# EthernetPlug.net
KiCad netlist of a schematic drawn in EAGLE
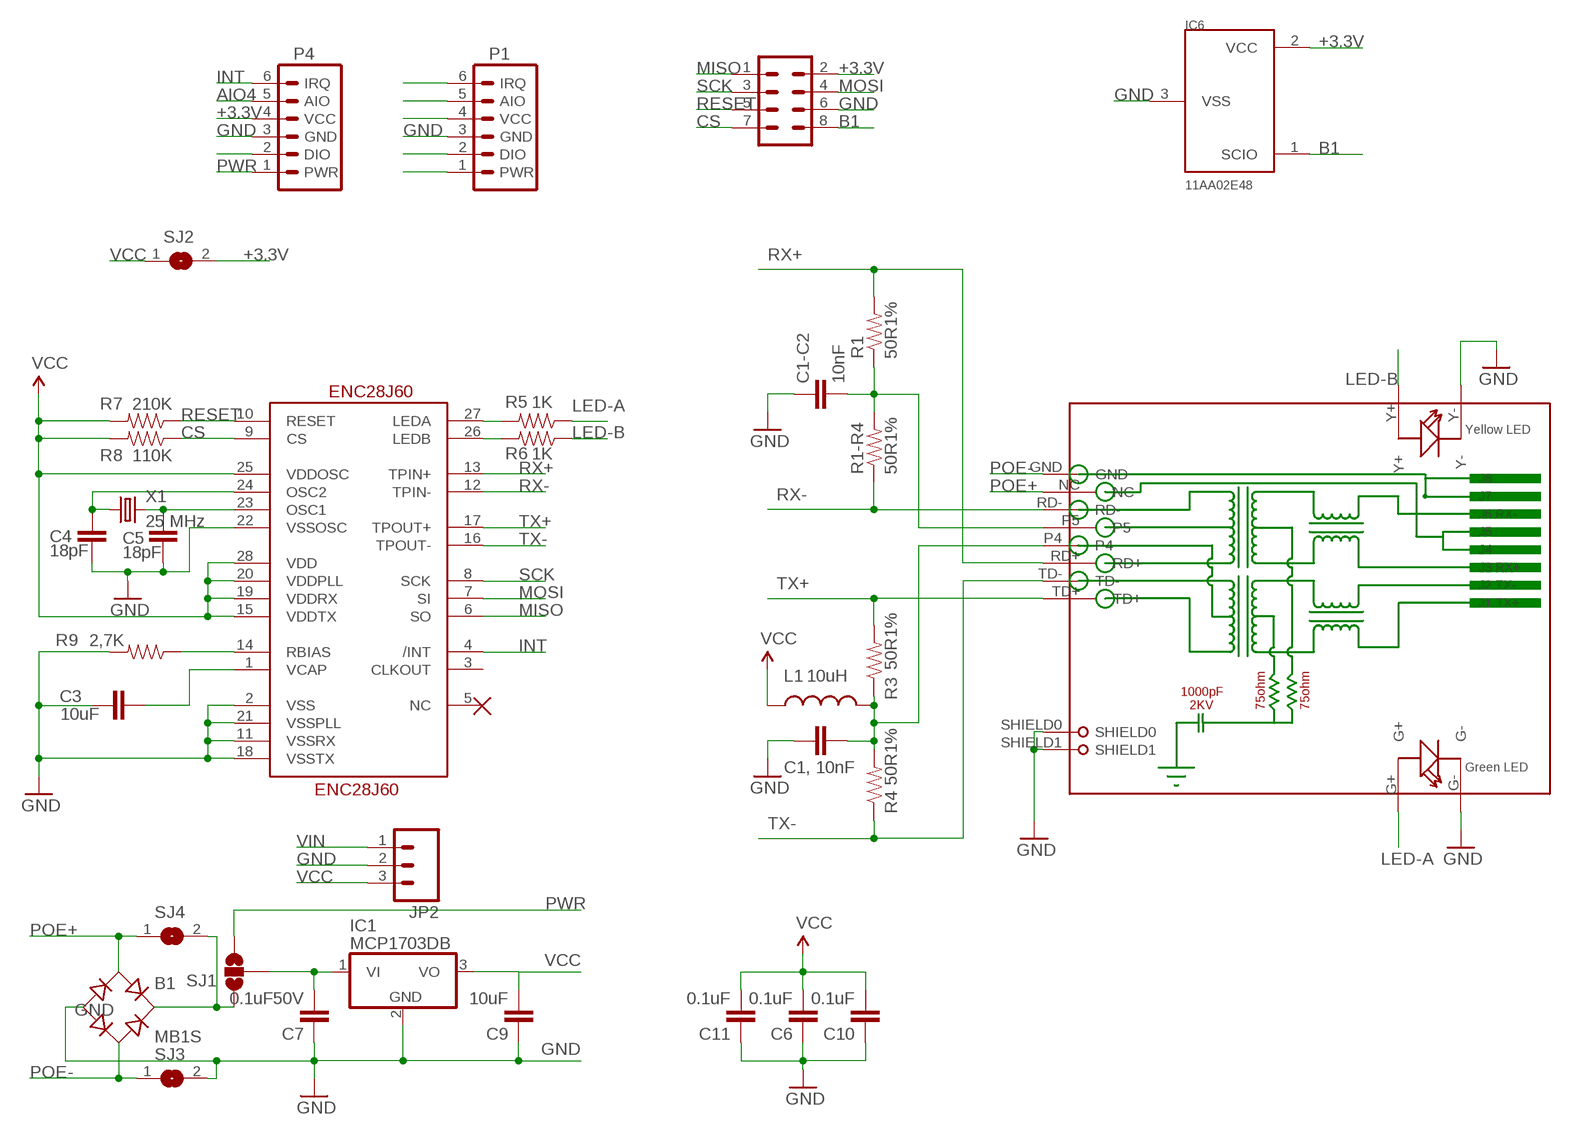
[diagram p0: schematic, sheet 1]

(export (version "E")
  (design (tool "Eeschema 10.0.6"))
  (components
    (comp (ref "B1")
      (value "MB1S")
      (footprint "eagle-import:SOIC-4")
      (libsource (lib "eagle-import") (part "MBS1"))
    )
    (comp (ref "C1,")
      (value "10nF")
      (footprint "eagle-import:0603-CAP")
      (libsource (lib "eagle-import") (part "CAP0603-CAP"))
    )
    (comp (ref "C1-C2")
      (value "10nF")
      (footprint "eagle-import:0603-CAP")
      (libsource (lib "eagle-import") (part "CAP0603-CAP"))
    )
    (comp (ref "C3")
      (value "10uF")
      (footprint "eagle-import:0603-CAP")
      (libsource (lib "eagle-import") (part "CAP0603-CAP"))
    )
    (comp (ref "C4")
      (value "18pF")
      (footprint "eagle-import:0603-CAP")
      (libsource (lib "eagle-import") (part "CAP0603-CAP"))
    )
    (comp (ref "C5")
      (value "18pF")
      (footprint "eagle-import:0603-CAP")
      (libsource (lib "eagle-import") (part "CAP0603-CAP"))
    )
    (comp (ref "C6")
      (value "0.1uF")
      (footprint "eagle-import:0603-CAP")
      (libsource (lib "eagle-import") (part "CAP0603-CAP"))
    )
    (comp (ref "C7")
      (value "0.1uF50V")
      (footprint "eagle-import:0603-CAP")
      (libsource (lib "eagle-import") (part "CAP0603-CAP"))
    )
    (comp (ref "C9")
      (value "10uF")
      (footprint "eagle-import:0603-CAP")
      (libsource (lib "eagle-import") (part "CAP0603-CAP"))
    )
    (comp (ref "C10")
      (value "0.1uF")
      (footprint "eagle-import:0603-CAP")
      (libsource (lib "eagle-import") (part "CAP0603-CAP"))
    )
    (comp (ref "C11")
      (value "0.1uF")
      (footprint "eagle-import:0603-CAP")
      (libsource (lib "eagle-import") (part "CAP0603-CAP"))
    )
    (comp (ref "ENC28J60")
      (value "ENC28J60")
      (footprint "eagle-import:SSOP28DB")
      (libsource (lib "eagle-import") (part "ENC28J60"))
    )
    (comp (ref "IC1")
      (value "MCP1703DB")
      (footprint "eagle-import:SOT223")
      (libsource (lib "eagle-import") (part "MCP1703DB"))
    )
    (comp (ref "IC6")
      (value "11AA02E48")
      (footprint "eagle-import:SOT23")
      (libsource (lib "eagle-import") (part "11AA02E48"))
    )
    (comp (ref "ISP")
      (value "MA04-2")
      (footprint "eagle-import:MA04-2")
      (libsource (lib "eagle-import") (part "MA04-2"))
    )
    (comp (ref "JP2")
      (value "M03PTH")
      (footprint "eagle-import:1X03")
      (libsource (lib "eagle-import") (part "M03PTH"))
    )
    (comp (ref "L1")
      (value "10uH")
      (footprint "eagle-import:0603")
      (libsource (lib "eagle-import") (part "INDUCTOR0603"))
    )
    (comp (ref "P1")
      (value "JEEPORT-FEMALE")
      (footprint "eagle-import:1X06_FEMALE_LOCK.010")
      (libsource (lib "eagle-import") (part "JEEPORT-FEMALE"))
    )
    (comp (ref "P4")
      (value "JEEPORT-FEMALE")
      (footprint "eagle-import:1X06_FEMALE_LOCK.010")
      (libsource (lib "eagle-import") (part "JEEPORT-FEMALE"))
    )
    (comp (ref "R1")
      (value "50R1%")
      (footprint "eagle-import:0603-RES")
      (libsource (lib "eagle-import") (part "RESISTOR0603-RES"))
    )
    (comp (ref "R1-R4")
      (value "50R1%")
      (footprint "eagle-import:0603-RES")
      (libsource (lib "eagle-import") (part "RESISTOR0603-RES"))
    )
    (comp (ref "R3")
      (value "50R1%")
      (footprint "eagle-import:0603-RES")
      (libsource (lib "eagle-import") (part "RESISTOR0603-RES"))
    )
    (comp (ref "R4")
      (value "50R1%")
      (footprint "eagle-import:0603-RES")
      (libsource (lib "eagle-import") (part "RESISTOR0603-RES"))
    )
    (comp (ref "R5")
      (value "1K")
      (footprint "eagle-import:0603-RES")
      (libsource (lib "eagle-import") (part "RESISTOR0603-RES"))
    )
    (comp (ref "R6")
      (value "1K")
      (footprint "eagle-import:0603-RES")
      (libsource (lib "eagle-import") (part "RESISTOR0603-RES"))
    )
    (comp (ref "R7")
      (value "210K")
      (footprint "eagle-import:0603-RES")
      (libsource (lib "eagle-import") (part "RESISTOR0603-RES"))
    )
    (comp (ref "R8")
      (value "110K")
      (footprint "eagle-import:0603-RES")
      (libsource (lib "eagle-import") (part "RESISTOR0603-RES"))
    )
    (comp (ref "R9")
      (value "2,7K")
      (footprint "eagle-import:0603-RES")
      (libsource (lib "eagle-import") (part "RESISTOR0603-RES"))
    )
    (comp (ref "RJ1")
      (value "HLJ-6115ANL")
      (footprint "eagle-import:HR911105A")
      (libsource (lib "eagle-import") (part "HLJ-6115ANL"))
    )
    (comp (ref "SJ1")
      (value "SOLDERJUMPER_2WAYT")
      (footprint "eagle-import:SJ_2")
      (libsource (lib "eagle-import") (part "SOLDERJUMPER_2WAYT"))
    )
    (comp (ref "SJ2") (value "SJ") (footprint "eagle-import:SJ") (libsource (lib "eagle-import") (part "SJ")))
    (comp (ref "SJ3") (value "SJ") (footprint "eagle-import:SJ") (libsource (lib "eagle-import") (part "SJ")))
    (comp (ref "SJ4") (value "SJ") (footprint "eagle-import:SJ") (libsource (lib "eagle-import") (part "SJ")))
    (comp (ref "X1")
      (value "25 MHz")
      (footprint "eagle-import:CRYSTAL-SMD-3.2X2.5")
      (libsource (lib "eagle-import") (part "CRYSTAL3.2X2.5"))
    )
  )
  (nets
    (net (code "1") (name "/+3.3V") (class "Default")
      (node (ref "IC6") (pin "2") (pinfunction "VCC_2") (pintype "bidirectional"))
      (node (ref "ISP") (pin "2") (pinfunction "2_2") (pintype "passive"))
      (node (ref "P4") (pin "4") (pinfunction "VCC_4") (pintype "power_in"))
      (node (ref "SJ2") (pin "2") (pinfunction "2_2") (pintype "passive"))
    )
    (net (code "2") (name "/AIO4") (class "Default")
      (node (ref "P4") (pin "5") (pinfunction "AIO_5") (pintype "bidirectional"))
    )
    (net (code "3") (name "/B1") (class "Default")
      (node (ref "IC6") (pin "1") (pinfunction "SCIO_1") (pintype "bidirectional"))
      (node (ref "ISP") (pin "8") (pinfunction "8_8") (pintype "passive"))
    )
    (net (code "4") (name "/CS") (class "Default")
      (node (ref "ENC28J60") (pin "9") (pinfunction "CS_9") (pintype "bidirectional"))
      (node (ref "ISP") (pin "7") (pinfunction "7_7") (pintype "passive"))
      (node (ref "R8") (pin "1") (pinfunction "1_1") (pintype "passive"))
    )
    (net (code "5") (name "/INT") (class "Default")
      (node (ref "ENC28J60") (pin "4") (pinfunction "/INT_4") (pintype "bidirectional"))
      (node (ref "P4") (pin "6") (pinfunction "IRQ_6") (pintype "bidirectional"))
    )
    (net (code "6") (name "/LED-A") (class "Default")
      (node (ref "R5") (pin "1") (pinfunction "1_1") (pintype "passive"))
      (node (ref "RJ1") (pin "G+") (pinfunction "G+_G+") (pintype "bidirectional"))
    )
    (net (code "7") (name "/LED-B") (class "Default")
      (node (ref "R6") (pin "1") (pinfunction "1_1") (pintype "passive"))
      (node (ref "RJ1") (pin "Y+") (pinfunction "Y+_Y+") (pintype "bidirectional"))
    )
    (net (code "8") (name "/MISO") (class "Default")
      (node (ref "ENC28J60") (pin "6") (pinfunction "SO_6") (pintype "bidirectional"))
      (node (ref "ISP") (pin "1") (pinfunction "1_1") (pintype "passive"))
    )
    (net (code "9") (name "/MOSI") (class "Default")
      (node (ref "ENC28J60") (pin "7") (pinfunction "SI_7") (pintype "bidirectional"))
      (node (ref "ISP") (pin "4") (pinfunction "4_4") (pintype "passive"))
    )
    (net (code "10") (name "/POE+") (class "Default")
      (node (ref "B1") (pin "~1") (pinfunction "AC1_~1") (pintype "passive"))
      (node (ref "RJ1") (pin "NC") (pinfunction "NC_NC") (pintype "bidirectional"))
      (node (ref "SJ4") (pin "1") (pinfunction "1_1") (pintype "passive"))
    )
    (net (code "11") (name "/POE-") (class "Default")
      (node (ref "B1") (pin "~2") (pinfunction "AC2_~2") (pintype "passive"))
      (node (ref "RJ1") (pin "GND") (pinfunction "GND_GND") (pintype "bidirectional"))
      (node (ref "SJ3") (pin "1") (pinfunction "1_1") (pintype "passive"))
    )
    (net (code "12") (name "/PWR") (class "Default")
      (node (ref "P4") (pin "1") (pinfunction "PWR_1") (pintype "power_in"))
      (node (ref "SJ1") (pin "3") (pinfunction "3_3") (pintype "passive"))
    )
    (net (code "13") (name "/RESET") (class "Default")
      (node (ref "ENC28J60") (pin "10") (pinfunction "RESET_10") (pintype "bidirectional"))
      (node (ref "ISP") (pin "5") (pinfunction "5_5") (pintype "passive"))
      (node (ref "R7") (pin "1") (pinfunction "1_1") (pintype "passive"))
    )
    (net (code "14") (name "/RX+") (class "Default")
      (node (ref "ENC28J60") (pin "13") (pinfunction "TPIN+_13") (pintype "bidirectional"))
      (node (ref "R1") (pin "2") (pinfunction "2_2") (pintype "passive"))
      (node (ref "RJ1") (pin "RD+") (pinfunction "RD+_RD+") (pintype "bidirectional"))
    )
    (net (code "15") (name "/RX-") (class "Default")
      (node (ref "ENC28J60") (pin "12") (pinfunction "TPIN-_12") (pintype "bidirectional"))
      (node (ref "R1-R4") (pin "1") (pinfunction "1_1") (pintype "passive"))
      (node (ref "RJ1") (pin "RD-") (pinfunction "RD-_RD-") (pintype "bidirectional"))
    )
    (net (code "16") (name "/SCK") (class "Default")
      (node (ref "ENC28J60") (pin "8") (pinfunction "SCK_8") (pintype "bidirectional"))
      (node (ref "ISP") (pin "3") (pinfunction "3_3") (pintype "passive"))
    )
    (net (code "17") (name "/TX+") (class "Default")
      (node (ref "ENC28J60") (pin "17") (pinfunction "TPOUT+_17") (pintype "bidirectional"))
      (node (ref "R3") (pin "2") (pinfunction "2_2") (pintype "passive"))
      (node (ref "RJ1") (pin "TD+") (pinfunction "TD+_TD+") (pintype "bidirectional"))
    )
    (net (code "18") (name "/TX-") (class "Default")
      (node (ref "ENC28J60") (pin "16") (pinfunction "TPOUT-_16") (pintype "bidirectional"))
      (node (ref "R4") (pin "1") (pinfunction "1_1") (pintype "passive"))
      (node (ref "RJ1") (pin "TD-") (pinfunction "TD-_TD-") (pintype "bidirectional"))
    )
    (net (code "19") (name "/VIN") (class "Default")
      (node (ref "C7") (pin "2") (pinfunction "2_2") (pintype "passive"))
      (node (ref "IC1") (pin "1") (pinfunction "VI_1") (pintype "input"))
      (node (ref "JP2") (pin "1") (pinfunction "1_1") (pintype "passive"))
      (node (ref "SJ1") (pin "2") (pinfunction "2_2") (pintype "passive"))
    )
    (net (code "20") (name "GND") (class "Default")
      (node (ref "B1") (pin "-") (pinfunction "-_-") (pintype "passive"))
      (node (ref "C1,") (pin "1") (pinfunction "1_1") (pintype "passive"))
      (node (ref "C1-C2") (pin "1") (pinfunction "1_1") (pintype "passive"))
      (node (ref "C10") (pin "1") (pinfunction "1_1") (pintype "passive"))
      (node (ref "C11") (pin "1") (pinfunction "1_1") (pintype "passive"))
      (node (ref "C3") (pin "1") (pinfunction "1_1") (pintype "passive"))
      (node (ref "C4") (pin "1") (pinfunction "1_1") (pintype "passive"))
      (node (ref "C5") (pin "1") (pinfunction "1_1") (pintype "passive"))
      (node (ref "C6") (pin "1") (pinfunction "1_1") (pintype "passive"))
      (node (ref "C7") (pin "1") (pinfunction "1_1") (pintype "passive"))
      (node (ref "C9") (pin "1") (pinfunction "1_1") (pintype "passive"))
      (node (ref "ENC28J60") (pin "11") (pinfunction "VSSRX_11") (pintype "bidirectional"))
      (node (ref "ENC28J60") (pin "18") (pinfunction "VSSTX_18") (pintype "bidirectional"))
      (node (ref "ENC28J60") (pin "2") (pinfunction "VSS_2") (pintype "bidirectional"))
      (node (ref "ENC28J60") (pin "21") (pinfunction "VSSPLL_21") (pintype "bidirectional"))
      (node (ref "ENC28J60") (pin "22") (pinfunction "VSSOSC_22") (pintype "bidirectional"))
      (node (ref "IC1") (pin "2") (pinfunction "GND_2") (pintype "passive"))
      (node (ref "IC6") (pin "3") (pinfunction "VSS_3") (pintype "bidirectional"))
      (node (ref "ISP") (pin "6") (pinfunction "6_6") (pintype "passive"))
      (node (ref "JP2") (pin "2") (pinfunction "2_2") (pintype "passive"))
      (node (ref "P1") (pin "3") (pinfunction "GND_3") (pintype "power_in"))
      (node (ref "P4") (pin "3") (pinfunction "GND_3") (pintype "power_in"))
      (node (ref "R9") (pin "2") (pinfunction "2_2") (pintype "passive"))
      (node (ref "RJ1") (pin "G-") (pinfunction "G-_G-") (pintype "bidirectional"))
      (node (ref "RJ1") (pin "SHIELD0") (pinfunction "SHIELD0_SHIELD0") (pintype "bidirectional"))
      (node (ref "RJ1") (pin "SHIELD1") (pinfunction "SHIELD1_SHIELD1") (pintype "bidirectional"))
      (node (ref "RJ1") (pin "Y-") (pinfunction "Y-_Y-") (pintype "bidirectional"))
      (node (ref "SJ3") (pin "2") (pinfunction "2_2") (pintype "passive"))
    )
    (net (code "21") (name "Net-(B1-Pad+)") (class "Default")
      (node (ref "B1") (pin "+") (pinfunction "+_+") (pintype "passive"))
      (node (ref "SJ1") (pin "1") (pinfunction "1_1") (pintype "passive"))
      (node (ref "SJ4") (pin "2") (pinfunction "2_2") (pintype "passive"))
    )
    (net (code "22") (name "Net-(C1,-Pad2)") (class "Default")
      (node (ref "C1,") (pin "2") (pinfunction "2_2") (pintype "passive"))
      (node (ref "L1") (pin "2") (pinfunction "2_2") (pintype "passive"))
      (node (ref "R3") (pin "1") (pinfunction "1_1") (pintype "passive"))
      (node (ref "R4") (pin "2") (pinfunction "2_2") (pintype "passive"))
      (node (ref "RJ1") (pin "P4") (pinfunction "P4_P4") (pintype "bidirectional"))
    )
    (net (code "23") (name "Net-(C1-C2-Pad2)") (class "Default")
      (node (ref "C1-C2") (pin "2") (pinfunction "2_2") (pintype "passive"))
      (node (ref "R1") (pin "1") (pinfunction "1_1") (pintype "passive"))
      (node (ref "R1-R4") (pin "2") (pinfunction "2_2") (pintype "passive"))
      (node (ref "RJ1") (pin "P5") (pinfunction "P5_P5") (pintype "bidirectional"))
    )
    (net (code "24") (name "Net-(ENC28J60-LEDA)") (class "Default")
      (node (ref "ENC28J60") (pin "27") (pinfunction "LEDA_27") (pintype "bidirectional"))
      (node (ref "R5") (pin "2") (pinfunction "2_2") (pintype "passive"))
    )
    (net (code "25") (name "Net-(ENC28J60-LEDB)") (class "Default")
      (node (ref "ENC28J60") (pin "26") (pinfunction "LEDB_26") (pintype "bidirectional"))
      (node (ref "R6") (pin "2") (pinfunction "2_2") (pintype "passive"))
    )
    (net (code "26") (name "Net-(ENC28J60-OSC1)") (class "Default")
      (node (ref "C5") (pin "2") (pinfunction "2_2") (pintype "passive"))
      (node (ref "ENC28J60") (pin "23") (pinfunction "OSC1_23") (pintype "bidirectional"))
      (node (ref "X1") (pin "3") (pinfunction "2_3") (pintype "passive"))
    )
    (net (code "27") (name "Net-(ENC28J60-OSC2)") (class "Default")
      (node (ref "C4") (pin "2") (pinfunction "2_2") (pintype "passive"))
      (node (ref "ENC28J60") (pin "24") (pinfunction "OSC2_24") (pintype "bidirectional"))
      (node (ref "X1") (pin "1") (pinfunction "1_1") (pintype "passive"))
    )
    (net (code "28") (name "Net-(ENC28J60-RBIAS)") (class "Default")
      (node (ref "ENC28J60") (pin "14") (pinfunction "RBIAS_14") (pintype "bidirectional"))
      (node (ref "R9") (pin "1") (pinfunction "1_1") (pintype "passive"))
    )
    (net (code "29") (name "Net-(ENC28J60-VCAP)") (class "Default")
      (node (ref "C3") (pin "2") (pinfunction "2_2") (pintype "passive"))
      (node (ref "ENC28J60") (pin "1") (pinfunction "VCAP_1") (pintype "bidirectional"))
    )
    (net (code "30") (name "VCC") (class "Default")
      (node (ref "C10") (pin "2") (pinfunction "2_2") (pintype "passive"))
      (node (ref "C11") (pin "2") (pinfunction "2_2") (pintype "passive"))
      (node (ref "C6") (pin "2") (pinfunction "2_2") (pintype "passive"))
      (node (ref "C9") (pin "2") (pinfunction "2_2") (pintype "passive"))
      (node (ref "ENC28J60") (pin "15") (pinfunction "VDDTX_15") (pintype "bidirectional"))
      (node (ref "ENC28J60") (pin "19") (pinfunction "VDDRX_19") (pintype "bidirectional"))
      (node (ref "ENC28J60") (pin "20") (pinfunction "VDDPLL_20") (pintype "bidirectional"))
      (node (ref "ENC28J60") (pin "25") (pinfunction "VDDOSC_25") (pintype "bidirectional"))
      (node (ref "ENC28J60") (pin "28") (pinfunction "VDD_28") (pintype "bidirectional"))
      (node (ref "IC1") (pin "3") (pinfunction "VO_3") (pintype "passive"))
      (node (ref "JP2") (pin "3") (pinfunction "3_3") (pintype "passive"))
      (node (ref "L1") (pin "1") (pinfunction "1_1") (pintype "passive"))
      (node (ref "R7") (pin "2") (pinfunction "2_2") (pintype "passive"))
      (node (ref "R8") (pin "2") (pinfunction "2_2") (pintype "passive"))
      (node (ref "SJ2") (pin "1") (pinfunction "1_1") (pintype "passive"))
    )
    (net (code "31") (name "unconnected-(ENC28J60-CLKOUT-Pad3)") (class "Default")
      (node (ref "ENC28J60") (pin "3") (pinfunction "CLKOUT_3") (pintype "bidirectional"))
    )
    (net (code "32") (name "unconnected-(ENC28J60-NC-Pad5)") (class "Default")
      (node (ref "ENC28J60") (pin "5") (pinfunction "NC_5") (pintype "bidirectional"))
    )
    (net (code "33") (name "unconnected-(P1-AIO-Pad5)") (class "Default")
      (node (ref "P1") (pin "5") (pinfunction "AIO_5") (pintype "bidirectional"))
    )
    (net (code "34") (name "unconnected-(P1-DIO-Pad2)") (class "Default")
      (node (ref "P1") (pin "2") (pinfunction "DIO_2") (pintype "bidirectional"))
    )
    (net (code "35") (name "unconnected-(P1-IRQ-Pad6)") (class "Default")
      (node (ref "P1") (pin "6") (pinfunction "IRQ_6") (pintype "bidirectional"))
    )
    (net (code "36") (name "unconnected-(P1-PWR-Pad1)") (class "Default")
      (node (ref "P1") (pin "1") (pinfunction "PWR_1") (pintype "power_in"))
    )
    (net (code "37") (name "unconnected-(P1-VCC-Pad4)") (class "Default")
      (node (ref "P1") (pin "4") (pinfunction "VCC_4") (pintype "power_in"))
    )
    (net (code "38") (name "unconnected-(P4-DIO-Pad2)") (class "Default")
      (node (ref "P4") (pin "2") (pinfunction "DIO_2") (pintype "bidirectional"))
    )
  )
)
